# Radio.net
KiCad netlist of a schematic drawn in Altium Designer
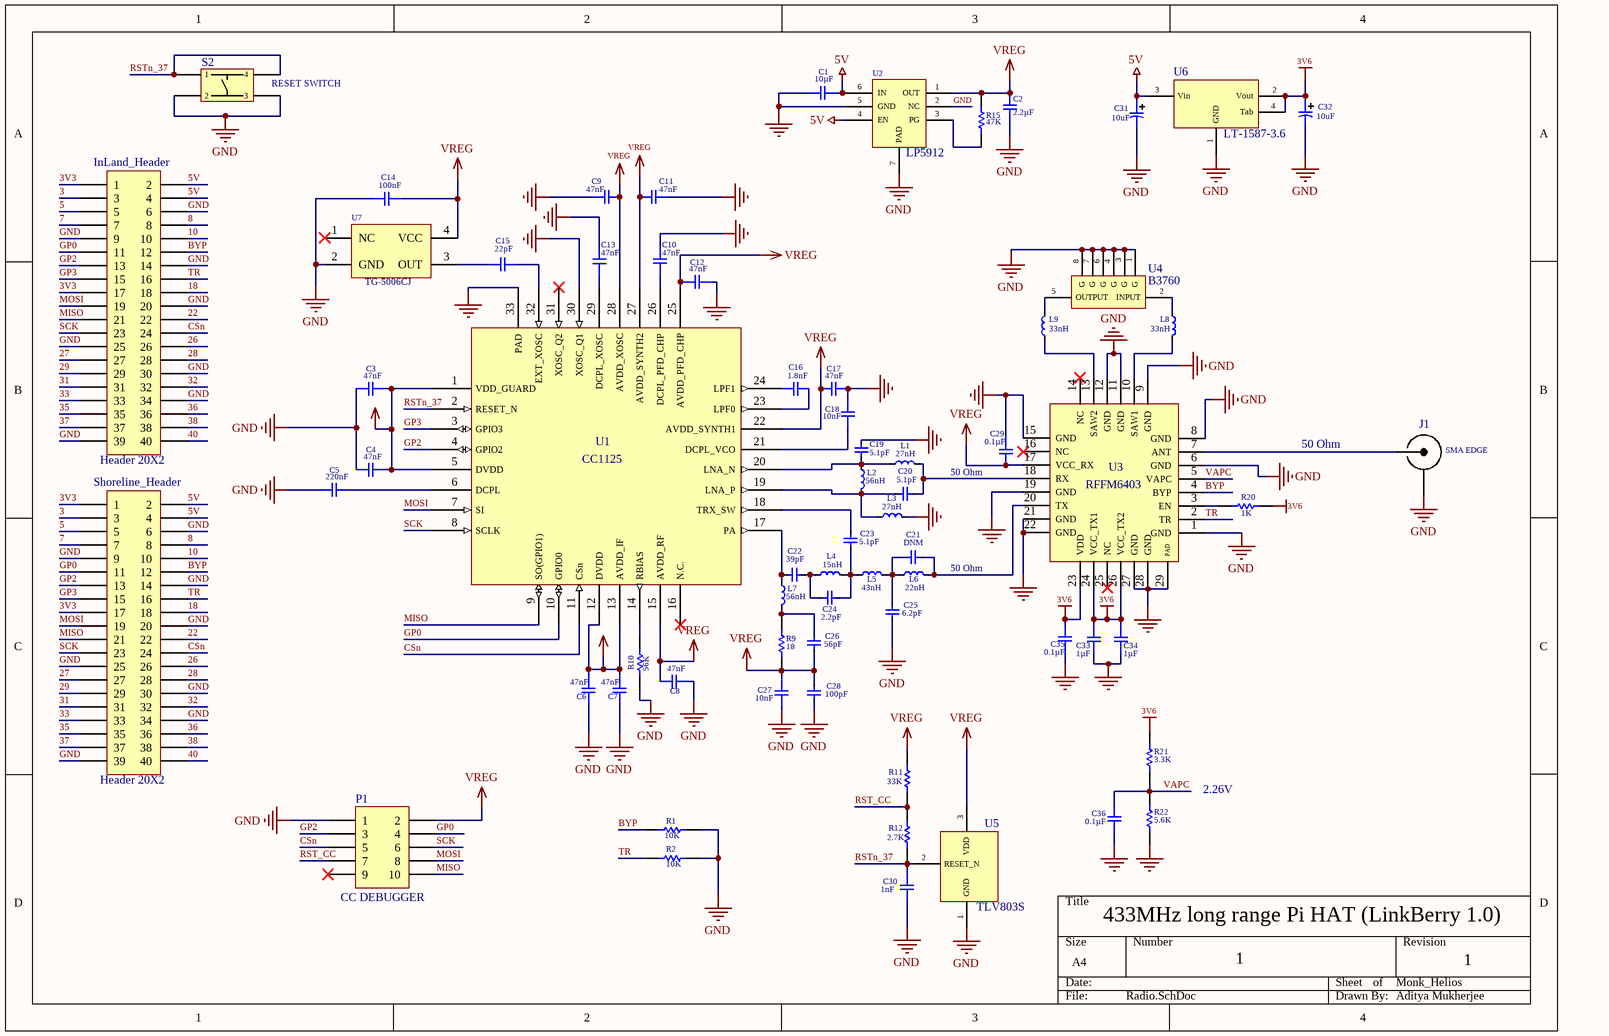
[diagram p0: Radio.SchDoc]

(export (version "E")
  (design (tool "Eeschema 10.0.6"))
  (components
    (comp (ref "C1")
      (value "10µF")
      (footprint "SMD-0603C")
      (description "CAP CER 0.1UF 16V X7R 0603")
      (fields
        (field (name "DIGI-KEY PART NUMBER") "490-5796-1-ND")
        (field (name "PART NUMBER") "GCJ188R71C104KA01D")
      )
      (libsource (lib "capacitor_murata_0603") (part "GCJ188R71C104KA01D"))
    )
    (comp (ref "C2")
      (value "2.2µF")
      (footprint "SMD-0603C")
      (description "CAP CER 0.1UF 16V X7R 0603")
      (fields
        (field (name "DIGI-KEY PART NUMBER") "490-5796-1-ND")
        (field (name "PART NUMBER") "GCJ188R71C104KA01D")
      )
      (libsource (lib "capacitor_murata_0603") (part "GCJ188R71C104KA01D"))
    )
    (comp (ref "C3")
      (value "47nF")
      (footprint "SMD-0402C")
      (description "CAP CER 1UF 10V X7S 0402")
      (fields
        (field (name "DIGI-KEY PART NUMBER") "490-13409-1-ND")
        (field (name "PART NUMBER") "GCM155C71A105KE38D")
      )
      (libsource (lib "capacitor_murata_0402") (part "GCM155C71A105KE38D"))
    )
    (comp (ref "C4")
      (value "47nF")
      (footprint "SMD-0402C")
      (description "CAP CER 1UF 10V X7S 0402")
      (fields
        (field (name "DIGI-KEY PART NUMBER") "490-13409-1-ND")
        (field (name "PART NUMBER") "GCM155C71A105KE38D")
      )
      (libsource (lib "capacitor_murata_0402") (part "GCM155C71A105KE38D"))
    )
    (comp (ref "C5")
      (value "220nF")
      (footprint "SMD-0402C")
      (description "CAP CER 1UF 10V X7S 0402")
      (fields
        (field (name "DIGI-KEY PART NUMBER") "490-13409-1-ND")
        (field (name "PART NUMBER") "GCM155C71A105KE38D")
      )
      (libsource (lib "capacitor_murata_0402") (part "GCM155C71A105KE38D"))
    )
    (comp (ref "C6")
      (value "47nF")
      (footprint "SMD-0402C")
      (description "CAP CER 1UF 10V X7S 0402")
      (fields
        (field (name "DIGI-KEY PART NUMBER") "490-13409-1-ND")
        (field (name "PART NUMBER") "GCM155C71A105KE38D")
      )
      (libsource (lib "capacitor_murata_0402") (part "GCM155C71A105KE38D"))
    )
    (comp (ref "C7")
      (value "47nF")
      (footprint "SMD-0402C")
      (description "CAP CER 1UF 10V X7S 0402")
      (fields
        (field (name "DIGI-KEY PART NUMBER") "490-13409-1-ND")
        (field (name "PART NUMBER") "GCM155C71A105KE38D")
      )
      (libsource (lib "capacitor_murata_0402") (part "GCM155C71A105KE38D"))
    )
    (comp (ref "C8")
      (value "47nF")
      (footprint "SMD-0402C")
      (description "CAP CER 1UF 10V X7S 0402")
      (fields
        (field (name "DIGI-KEY PART NUMBER") "490-13409-1-ND")
        (field (name "PART NUMBER") "GCM155C71A105KE38D")
      )
      (libsource (lib "capacitor_murata_0402") (part "GCM155C71A105KE38D"))
    )
    (comp (ref "C9")
      (value "47nF")
      (footprint "SMD-0402C")
      (description "CAP CER 1UF 10V X7S 0402")
      (fields
        (field (name "DIGI-KEY PART NUMBER") "490-13409-1-ND")
        (field (name "PART NUMBER") "GCM155C71A105KE38D")
      )
      (libsource (lib "capacitor_murata_0402") (part "GCM155C71A105KE38D"))
    )
    (comp (ref "C10")
      (value "47nF")
      (footprint "SMD-0402C")
      (description "CAP CER 1UF 10V X7S 0402")
      (fields
        (field (name "DIGI-KEY PART NUMBER") "490-13409-1-ND")
        (field (name "PART NUMBER") "GCM155C71A105KE38D")
      )
      (libsource (lib "capacitor_murata_0402") (part "GCM155C71A105KE38D"))
    )
    (comp (ref "C11")
      (value "47nF")
      (footprint "SMD-0402C")
      (description "CAP CER 1UF 10V X7S 0402")
      (fields
        (field (name "DIGI-KEY PART NUMBER") "490-13409-1-ND")
        (field (name "PART NUMBER") "GCM155C71A105KE38D")
      )
      (libsource (lib "capacitor_murata_0402") (part "GCM155C71A105KE38D"))
    )
    (comp (ref "C12")
      (value "47nF")
      (footprint "SMD-0402C")
      (description "CAP CER 1UF 10V X7S 0402")
      (fields
        (field (name "DIGI-KEY PART NUMBER") "490-13409-1-ND")
        (field (name "PART NUMBER") "GCM155C71A105KE38D")
      )
      (libsource (lib "capacitor_murata_0402") (part "GCM155C71A105KE38D"))
    )
    (comp (ref "C13")
      (value "47nF")
      (footprint "SMD-0402C")
      (description "CAP CER 1UF 10V X7S 0402")
      (fields
        (field (name "DIGI-KEY PART NUMBER") "490-13409-1-ND")
        (field (name "PART NUMBER") "GCM155C71A105KE38D")
      )
      (libsource (lib "capacitor_murata_0402") (part "GCM155C71A105KE38D"))
    )
    (comp (ref "C14")
      (value "100nF")
      (footprint "SMD-0402C")
      (description "CAP CER 1UF 10V X7S 0402")
      (fields
        (field (name "DIGI-KEY PART NUMBER") "490-13409-1-ND")
        (field (name "PART NUMBER") "GCM155C71A105KE38D")
      )
      (libsource (lib "capacitor_murata_0402") (part "GCM155C71A105KE38D"))
    )
    (comp (ref "C15")
      (value "22pF")
      (footprint "SMD-0402C")
      (description "CAP CER 1UF 50V NP0 0402")
      (fields
        (field (name "DIGI-KEY PART NUMBER") "490-13409-1-ND")
        (field (name "PART NUMBER") "GCM155C71A105KE38D")
      )
      (libsource (lib "capacitor_murata_0402") (part "GCM155C71A105KE38D"))
    )
    (comp (ref "C16")
      (value "1.8nF")
      (footprint "SMD-0402C")
      (description "CAP CER 1.8nF 10V X7S 0402")
      (fields
        (field (name "DIGI-KEY PART NUMBER") "490-13409-1-ND")
        (field (name "PART NUMBER") "GCM155C71A105KE38D")
      )
      (libsource (lib "capacitor_murata_0402") (part "GCM155C71A105KE38D"))
    )
    (comp (ref "C17")
      (value "47nF")
      (footprint "SMD-0402C")
      (description "CAP CER 1UF 10V X7S 0402")
      (fields
        (field (name "DIGI-KEY PART NUMBER") "490-13409-1-ND")
        (field (name "PART NUMBER") "GCM155C71A105KE38D")
      )
      (libsource (lib "capacitor_murata_0402") (part "GCM155C71A105KE38D"))
    )
    (comp (ref "C18")
      (value "10nF")
      (footprint "SMD-0402C")
      (description "CAP CER 1UF 10V X7S 0402")
      (fields
        (field (name "DIGI-KEY PART NUMBER") "490-13409-1-ND")
        (field (name "PART NUMBER") "GCM155C71A105KE38D")
      )
      (libsource (lib "capacitor_murata_0402") (part "GCM155C71A105KE38D"))
    )
    (comp (ref "C19")
      (value "5.1pF")
      (footprint "0402")
      (description "Ceramic Chip Capacitor - Standard")
      (fields (field (name "Comment") "C0402") (field (name "PUBLISHER") "Altium Limited"))
      (libsource (lib "KEMET Chip Capacitor") (part "C0402"))
    )
    (comp (ref "C20")
      (value "5.1pF")
      (footprint "0402")
      (description "Ceramic Chip Capacitor - Standard")
      (fields (field (name "Comment") "C0402") (field (name "PUBLISHER") "Altium Limited"))
      (libsource (lib "KEMET Chip Capacitor") (part "C0402"))
    )
    (comp (ref "C21")
      (value "DNM")
      (footprint "0402")
      (description "Ceramic Chip Capacitor - Standard")
      (fields (field (name "Comment") "C0402") (field (name "PUBLISHER") "Altium Limited"))
      (libsource (lib "KEMET Chip Capacitor") (part "C0402"))
    )
    (comp (ref "C22")
      (value "39pF")
      (footprint "0402")
      (description "Ceramic Chip Capacitor - Standard")
      (fields (field (name "Comment") "C0402") (field (name "PUBLISHER") "Altium Limited"))
      (libsource (lib "KEMET Chip Capacitor") (part "C0402"))
    )
    (comp (ref "C23")
      (value "5.1pF")
      (footprint "0402")
      (description "Ceramic Chip Capacitor - Standard")
      (fields (field (name "Comment") "C0402") (field (name "PUBLISHER") "Altium Limited"))
      (libsource (lib "KEMET Chip Capacitor") (part "C0402"))
    )
    (comp (ref "C24")
      (value "2.2pF")
      (footprint "0402")
      (description "Ceramic Chip Capacitor - Standard")
      (fields (field (name "Comment") "C0402") (field (name "PUBLISHER") "Altium Limited"))
      (libsource (lib "KEMET Chip Capacitor") (part "C0402"))
    )
    (comp (ref "C25")
      (value "6.2pF")
      (footprint "0402")
      (description "Ceramic Chip Capacitor - Standard")
      (fields (field (name "Comment") "C0402") (field (name "PUBLISHER") "Altium Limited"))
      (libsource (lib "KEMET Chip Capacitor") (part "C0402"))
    )
    (comp (ref "C26")
      (value "56pF")
      (footprint "0402")
      (description "Ceramic Chip Capacitor - Standard")
      (fields (field (name "Comment") "C0402") (field (name "PUBLISHER") "Altium Limited"))
      (libsource (lib "KEMET Chip Capacitor") (part "C0402"))
    )
    (comp (ref "C27")
      (value "10nF")
      (footprint "SMD-0402C")
      (description "CAP CER 1UF 10V X7S 0402")
      (fields
        (field (name "DIGI-KEY PART NUMBER") "490-13409-1-ND")
        (field (name "PART NUMBER") "GCM155C71A105KE38D")
      )
      (libsource (lib "capacitor_murata_0402") (part "GCM155C71A105KE38D"))
    )
    (comp (ref "C28")
      (value "100pF")
      (footprint "0402")
      (description "Ceramic Chip Capacitor - Standard")
      (fields (field (name "Comment") "C0402") (field (name "PUBLISHER") "Altium Limited"))
      (libsource (lib "KEMET Chip Capacitor") (part "C0402"))
    )
    (comp (ref "C29")
      (value "0.1µF")
      (footprint "SMD-0603C")
      (description "CAP CER 0.1UF 16V X7R 0603")
      (fields
        (field (name "DIGI-KEY PART NUMBER") "490-5796-1-ND")
        (field (name "PART NUMBER") "GCJ188R71C104KA01D")
      )
      (libsource (lib "capacitor_murata_0603") (part "GCJ188R71C104KA01D"))
    )
    (comp (ref "C30")
      (value "1nF")
      (footprint "SMD-0402C")
      (description "CAP CER 1UF 10V X7S 0402")
      (fields
        (field (name "DIGI-KEY PART NUMBER") "490-13409-1-ND")
        (field (name "PART NUMBER") "GCM155C71A105KE38D")
      )
      (libsource (lib "capacitor_murata_0402") (part "GCM155C71A105KE38D"))
    )
    (comp (ref "C31")
      (value "Component_1")
      (footprint "PCBComponent_1")
      (fields (field (name "ALTIUM_UNNAMED_1") "10uF"))
      (libsource (lib "AVX_tantalium_1505") (part "Component_1"))
    )
    (comp (ref "C32")
      (value "Component_1")
      (footprint "PCBComponent_1")
      (fields (field (name "ALTIUM_UNNAMED_1") "10uF"))
      (libsource (lib "AVX_tantalium_1505") (part "Component_1"))
    )
    (comp (ref "C33")
      (value "1µF")
      (footprint "SMD-0603C")
      (description "CAP CER 1UF 16V X7R 0603")
      (fields
        (field (name "DIGI-KEY PART NUMBER") "490-5796-1-ND")
        (field (name "PART NUMBER") "GCJ188R71C104KA01D")
      )
      (libsource (lib "capacitor_murata_0603") (part "GCJ188R71C104KA01D"))
    )
    (comp (ref "C34")
      (value "1µF")
      (footprint "SMD-0603C")
      (description "CAP CER 1UF 16V X7R 0603")
      (fields
        (field (name "DIGI-KEY PART NUMBER") "490-5796-1-ND")
        (field (name "PART NUMBER") "GCJ188R71C104KA01D")
      )
      (libsource (lib "capacitor_murata_0603") (part "GCJ188R71C104KA01D"))
    )
    (comp (ref "C35")
      (value "0.1µF")
      (footprint "SMD-0603C")
      (description "CAP CER 0.1UF 16V X7R 0603")
      (fields
        (field (name "DIGI-KEY PART NUMBER") "490-5796-1-ND")
        (field (name "PART NUMBER") "GCJ188R71C104KA01D")
      )
      (libsource (lib "capacitor_murata_0603") (part "GCJ188R71C104KA01D"))
    )
    (comp (ref "C36")
      (value "0.1µF")
      (footprint "SMD-0603C")
      (description "CAP CER 0.1UF 16V X7R 0603")
      (fields
        (field (name "DIGI-KEY PART NUMBER") "490-5796-1-ND")
        (field (name "PART NUMBER") "GCJ188R71C104KA01D")
      )
      (libsource (lib "capacitor_murata_0603") (part "GCJ188R71C104KA01D"))
    )
    (comp (ref "InLand_Header")
      (value "Header 20X2")
      (footprint "HDR2X20")
      (description "Header, 20-Pin, Dual row")
      (fields (field (name "PUBLISHER") "Altium Limited"))
      (libsource (lib "Miscellaneous Connectors") (part "Header 20X2"))
    )
    (comp (ref "J1")
      (value "SMA EDGE")
      (footprint "PCBComponent_1")
      (libsource (lib "SMA_small") (part "Component_1"))
    )
    (comp (ref "L1")
      (value "Component_1")
      (footprint "LQW15AN80")
      (fields (field (name "ALTIUM_UNNAMED_1") "27nH"))
      (libsource (lib "LQW15AN80") (part "Component_1"))
    )
    (comp (ref "L2")
      (value "Component_1")
      (footprint "LQW15AW80")
      (fields (field (name "ALTIUM_UNNAMED_1") "56nH"))
      (libsource (lib "LQW15AW80") (part "Component_1"))
    )
    (comp (ref "L3")
      (value "Component_1")
      (footprint "LQW15AN80")
      (fields (field (name "ALTIUM_UNNAMED_1") "27nH"))
      (libsource (lib "LQW15AN80") (part "Component_1"))
    )
    (comp (ref "L4")
      (value "Component_1")
      (footprint "LQW15AN80")
      (fields (field (name "ALTIUM_UNNAMED_1") "15nH"))
      (libsource (lib "LQW15AN80") (part "Component_1"))
    )
    (comp (ref "L5")
      (value "Component_1")
      (footprint "LQW15AN80")
      (fields (field (name "ALTIUM_UNNAMED_1") "43nH"))
      (libsource (lib "LQW15AN80") (part "Component_1"))
    )
    (comp (ref "L6")
      (value "Component_1")
      (footprint "LQW15AN80")
      (fields (field (name "ALTIUM_UNNAMED_1") "22nH"))
      (libsource (lib "LQW15AN80") (part "Component_1"))
    )
    (comp (ref "L7")
      (value "Component_1")
      (footprint "LQW15AW80")
      (fields (field (name "ALTIUM_UNNAMED_1") "56nH"))
      (libsource (lib "LQW15AW80") (part "Component_1"))
    )
    (comp (ref "L8")
      (value "Component_1")
      (footprint "LQW15AN80")
      (fields (field (name "ALTIUM_UNNAMED_1") "33nH"))
      (libsource (lib "LQW15AN80") (part "Component_1"))
    )
    (comp (ref "L9")
      (value "Component_1")
      (footprint "LQW15AN80")
      (fields (field (name "ALTIUM_UNNAMED_1") "33nH"))
      (libsource (lib "LQW15AN80") (part "Component_1"))
    )
    (comp (ref "P1")
      (value "CC DEBUGGER")
      (footprint "HDR2X5")
      (description "Header, 5-Pin, Dual row")
      (fields (field (name "PUBLISHER") "Altium Limited"))
      (libsource (lib "Miscellaneous Connectors") (part "Header 5X2"))
    )
    (comp (ref "R1")
      (value "10K")
      (footprint "2-0402")
      (fields (field (name "ALTIUM_UNNAMED_1") "10K") (field (name "PUBLISHER") "Altium Limited"))
      (libsource (lib "Panasonic Resistor") (part "ERJ2RE"))
    )
    (comp (ref "R2")
      (value "10K")
      (footprint "2-0402")
      (fields (field (name "ALTIUM_UNNAMED_1") "10K") (field (name "PUBLISHER") "Altium Limited"))
      (libsource (lib "Panasonic Resistor") (part "ERJ2RE"))
    )
    (comp (ref "R9")
      (value "18")
      (footprint "2-0402")
      (description "Thick Film Chip Resistor, 1 Ohm to 2.2M Ohm Range, 5% Tolerance, 0402 Size, 0.063 W")
      (fields (field (name "Comment") "ERJ2GE") (field (name "PUBLISHER") "Altium Limited"))
      (libsource (lib "Panasonic Resistor") (part "ERJ2GE"))
    )
    (comp (ref "R10")
      (value "56K")
      (footprint "2-0402")
      (description "Thick Film Chip Resistor, 1 Ohm to 2.2M Ohm Range, 5% Tolerance, 0402 Size, 0.063 W")
      (fields (field (name "Comment") "ERJ2GE") (field (name "PUBLISHER") "Altium Limited"))
      (libsource (lib "Panasonic Resistor") (part "ERJ2GE"))
    )
    (comp (ref "R11")
      (value "10K")
      (footprint "2-0402")
      (fields (field (name "ALTIUM_UNNAMED_1") "33K") (field (name "PUBLISHER") "Altium Limited"))
      (libsource (lib "Panasonic Resistor") (part "ERJ2RE"))
    )
    (comp (ref "R12")
      (value "10K")
      (footprint "2-0402")
      (fields (field (name "ALTIUM_UNNAMED_1") "2.7K") (field (name "PUBLISHER") "Altium Limited"))
      (libsource (lib "Panasonic Resistor") (part "ERJ2RE"))
    )
    (comp (ref "R15")
      (value "47K")
      (footprint "ERA-0603")
      (fields (field (name "Comment") "ERA3Y") (field (name "PUBLISHER") "Altium Limited"))
      (libsource (lib "Panasonic Resistor") (part "ERA3Y"))
    )
    (comp (ref "R20")
      (value "1K")
      (footprint "2-0402")
      (description "Thick Film Chip Resistor, 1 Ohm to 2.2M Ohm Range, 5% Tolerance, 0402 Size, 0.063 W")
      (fields (field (name "Comment") "ERJ2GE") (field (name "PUBLISHER") "Altium Limited"))
      (libsource (lib "Panasonic Resistor") (part "ERJ2GE"))
    )
    (comp (ref "R21")
      (value "3.3K")
      (footprint "2-0402")
      (description "Thick Film Chip Resistor, 1 Ohm to 2.2M Ohm Range, 5% Tolerance, 0402 Size, 0.063 W")
      (fields (field (name "Comment") "ERJ2GE") (field (name "PUBLISHER") "Altium Limited"))
      (libsource (lib "Panasonic Resistor") (part "ERJ2GE"))
    )
    (comp (ref "R22")
      (value "5.6K")
      (footprint "2-0402")
      (description "Thick Film Chip Resistor, 1 Ohm to 2.2M Ohm Range, 5% Tolerance, 0402 Size, 0.063 W")
      (fields (field (name "Comment") "ERJ2GE") (field (name "PUBLISHER") "Altium Limited"))
      (libsource (lib "Panasonic Resistor") (part "ERJ2GE"))
    )
    (comp (ref "S2")
      (value "RESET SWITCH")
      (footprint "PCBComponent_1")
      (libsource (lib "panasonic_90deg_tactile") (part "Component_1"))
    )
    (comp (ref "Shoreline_Header")
      (value "Header 20X2")
      (footprint "HDR2X20")
      (description "Header, 20-Pin, Dual row")
      (fields (field (name "PUBLISHER") "Altium Limited"))
      (libsource (lib "Miscellaneous Connectors") (part "Header 20X2"))
    )
    (comp (ref "U1") (value "CC1125") (footprint "CC1125 QFN") (libsource (lib "CC1125") (part "CC1125")))
    (comp (ref "U2") (value "LP5912") (footprint "LP5912_WSON") (libsource (lib "5912") (part "LP5912")))
    (comp (ref "U3")
      (value "RFFM6403")
      (footprint "PCBComponent_1")
      (libsource (lib "RFFM6403") (part "RFFM6403"))
    )
    (comp (ref "U4")
      (value "B3760")
      (footprint "PCBComponent_1")
      (libsource (lib "B3760_SAW_filter") (part "Component_1"))
    )
    (comp (ref "U5")
      (value "TLV803S")
      (footprint "SOT95P237X110-3N")
      (libsource (lib "TLV803S") (part "Component_1"))
    )
    (comp (ref "U6")
      (value "LT1587-3.6")
      (footprint "LT1587")
      (fields (field (name "ALTIUM_UNNAMED_1") "LT-1587-3.6"))
      (libsource (lib "LT1587-3.6") (part "Component_1"))
    )
    (comp (ref "U7")
      (value "TG-5006CJ")
      (footprint "TG-5006CJ")
      (libsource (lib "TG-5006(TCXO)") (part "TG-5006CJ"))
    )
  )
  (nets
    (net (code "1") (name "/3") (class "Default")
      (node (ref "InLand_Header") (pin "3") (pinfunction "3_3") (pintype "passive"))
      (node (ref "Shoreline_Header") (pin "3") (pinfunction "3_3") (pintype "passive"))
    )
    (net (code "2") (name "/3V3") (class "Default")
      (node (ref "InLand_Header") (pin "1") (pinfunction "1_1") (pintype "passive"))
      (node (ref "InLand_Header") (pin "17") (pinfunction "17_17") (pintype "passive"))
      (node (ref "Shoreline_Header") (pin "1") (pinfunction "1_1") (pintype "passive"))
      (node (ref "Shoreline_Header") (pin "17") (pinfunction "17_17") (pintype "passive"))
    )
    (net (code "3") (name "/5") (class "Default")
      (node (ref "InLand_Header") (pin "5") (pinfunction "5_5") (pintype "passive"))
      (node (ref "Shoreline_Header") (pin "5") (pinfunction "5_5") (pintype "passive"))
    )
    (net (code "4") (name "/7") (class "Default")
      (node (ref "InLand_Header") (pin "7") (pinfunction "7_7") (pintype "passive"))
      (node (ref "Shoreline_Header") (pin "7") (pinfunction "7_7") (pintype "passive"))
    )
    (net (code "5") (name "/8") (class "Default")
      (node (ref "InLand_Header") (pin "8") (pinfunction "8_8") (pintype "passive"))
      (node (ref "Shoreline_Header") (pin "8") (pinfunction "8_8") (pintype "passive"))
    )
    (net (code "6") (name "/10") (class "Default")
      (node (ref "InLand_Header") (pin "10") (pinfunction "10_10") (pintype "passive"))
      (node (ref "Shoreline_Header") (pin "10") (pinfunction "10_10") (pintype "passive"))
    )
    (net (code "7") (name "/18") (class "Default")
      (node (ref "InLand_Header") (pin "18") (pinfunction "18_18") (pintype "passive"))
      (node (ref "Shoreline_Header") (pin "18") (pinfunction "18_18") (pintype "passive"))
    )
    (net (code "8") (name "/22") (class "Default")
      (node (ref "InLand_Header") (pin "22") (pinfunction "22_22") (pintype "passive"))
      (node (ref "Shoreline_Header") (pin "22") (pinfunction "22_22") (pintype "passive"))
    )
    (net (code "9") (name "/26") (class "Default")
      (node (ref "InLand_Header") (pin "26") (pinfunction "26_26") (pintype "passive"))
      (node (ref "Shoreline_Header") (pin "26") (pinfunction "26_26") (pintype "passive"))
    )
    (net (code "10") (name "/27") (class "Default")
      (node (ref "InLand_Header") (pin "27") (pinfunction "27_27") (pintype "passive"))
      (node (ref "Shoreline_Header") (pin "27") (pinfunction "27_27") (pintype "passive"))
    )
    (net (code "11") (name "/28") (class "Default")
      (node (ref "InLand_Header") (pin "28") (pinfunction "28_28") (pintype "passive"))
      (node (ref "Shoreline_Header") (pin "28") (pinfunction "28_28") (pintype "passive"))
    )
    (net (code "12") (name "/29") (class "Default")
      (node (ref "InLand_Header") (pin "29") (pinfunction "29_29") (pintype "passive"))
      (node (ref "Shoreline_Header") (pin "29") (pinfunction "29_29") (pintype "passive"))
    )
    (net (code "13") (name "/31") (class "Default")
      (node (ref "InLand_Header") (pin "31") (pinfunction "31_31") (pintype "passive"))
      (node (ref "Shoreline_Header") (pin "31") (pinfunction "31_31") (pintype "passive"))
    )
    (net (code "14") (name "/32") (class "Default")
      (node (ref "InLand_Header") (pin "32") (pinfunction "32_32") (pintype "passive"))
      (node (ref "Shoreline_Header") (pin "32") (pinfunction "32_32") (pintype "passive"))
    )
    (net (code "15") (name "/33") (class "Default")
      (node (ref "InLand_Header") (pin "33") (pinfunction "33_33") (pintype "passive"))
      (node (ref "Shoreline_Header") (pin "33") (pinfunction "33_33") (pintype "passive"))
    )
    (net (code "16") (name "/35") (class "Default")
      (node (ref "InLand_Header") (pin "35") (pinfunction "35_35") (pintype "passive"))
      (node (ref "Shoreline_Header") (pin "35") (pinfunction "35_35") (pintype "passive"))
    )
    (net (code "17") (name "/36") (class "Default")
      (node (ref "InLand_Header") (pin "36") (pinfunction "36_36") (pintype "passive"))
      (node (ref "Shoreline_Header") (pin "36") (pinfunction "36_36") (pintype "passive"))
    )
    (net (code "18") (name "/37") (class "Default")
      (node (ref "InLand_Header") (pin "37") (pinfunction "37_37") (pintype "passive"))
      (node (ref "Shoreline_Header") (pin "37") (pinfunction "37_37") (pintype "passive"))
    )
    (net (code "19") (name "/38") (class "Default")
      (node (ref "InLand_Header") (pin "38") (pinfunction "38_38") (pintype "passive"))
      (node (ref "Shoreline_Header") (pin "38") (pinfunction "38_38") (pintype "passive"))
    )
    (net (code "20") (name "/40") (class "Default")
      (node (ref "InLand_Header") (pin "40") (pinfunction "40_40") (pintype "passive"))
      (node (ref "Shoreline_Header") (pin "40") (pinfunction "40_40") (pintype "passive"))
    )
    (net (code "21") (name "/BYP") (class "Default")
      (node (ref "InLand_Header") (pin "12") (pinfunction "12_12") (pintype "passive"))
      (node (ref "R1") (pin "2") (pinfunction "2_2") (pintype "passive"))
      (node (ref "Shoreline_Header") (pin "12") (pinfunction "12_12") (pintype "passive"))
      (node (ref "U3") (pin "4") (pinfunction "BYP_4") (pintype "passive"))
    )
    (net (code "22") (name "/CSn") (class "Default")
      (node (ref "InLand_Header") (pin "24") (pinfunction "24_24") (pintype "passive"))
      (node (ref "P1") (pin "5") (pinfunction "5_5") (pintype "passive"))
      (node (ref "Shoreline_Header") (pin "24") (pinfunction "24_24") (pintype "passive"))
      (node (ref "U1") (pin "11") (pinfunction "CSn_11") (pintype "input"))
    )
    (net (code "23") (name "/GP0") (class "Default")
      (node (ref "InLand_Header") (pin "11") (pinfunction "11_11") (pintype "passive"))
      (node (ref "P1") (pin "4") (pinfunction "4_4") (pintype "passive"))
      (node (ref "Shoreline_Header") (pin "11") (pinfunction "11_11") (pintype "passive"))
      (node (ref "U1") (pin "10") (pinfunction "GPIO0_10") (pintype "bidirectional"))
    )
    (net (code "24") (name "/GP2") (class "Default")
      (node (ref "InLand_Header") (pin "13") (pinfunction "13_13") (pintype "passive"))
      (node (ref "P1") (pin "3") (pinfunction "3_3") (pintype "passive"))
      (node (ref "Shoreline_Header") (pin "13") (pinfunction "13_13") (pintype "passive"))
      (node (ref "U1") (pin "4") (pinfunction "GPIO2_4") (pintype "bidirectional"))
    )
    (net (code "25") (name "/GP3") (class "Default")
      (node (ref "InLand_Header") (pin "15") (pinfunction "15_15") (pintype "passive"))
      (node (ref "Shoreline_Header") (pin "15") (pinfunction "15_15") (pintype "passive"))
      (node (ref "U1") (pin "3") (pinfunction "GPIO3_3") (pintype "bidirectional"))
    )
    (net (code "26") (name "/MISO") (class "Default")
      (node (ref "InLand_Header") (pin "21") (pinfunction "21_21") (pintype "passive"))
      (node (ref "P1") (pin "10") (pinfunction "10_10") (pintype "passive"))
      (node (ref "Shoreline_Header") (pin "21") (pinfunction "21_21") (pintype "passive"))
      (node (ref "U1") (pin "9") (pinfunction "SO(GPIO1)_9") (pintype "bidirectional"))
    )
    (net (code "27") (name "/MOSI") (class "Default")
      (node (ref "InLand_Header") (pin "19") (pinfunction "19_19") (pintype "passive"))
      (node (ref "P1") (pin "8") (pinfunction "8_8") (pintype "passive"))
      (node (ref "Shoreline_Header") (pin "19") (pinfunction "19_19") (pintype "passive"))
      (node (ref "U1") (pin "7") (pinfunction "SI_7") (pintype "input"))
    )
    (net (code "28") (name "/RST_CC") (class "Default")
      (node (ref "P1") (pin "7") (pinfunction "7_7") (pintype "passive"))
      (node (ref "R11") (pin "1") (pinfunction "1_1") (pintype "passive"))
      (node (ref "R12") (pin "2") (pinfunction "2_2") (pintype "passive"))
    )
    (net (code "29") (name "/RSTn_37") (class "Default")
      (node (ref "C30") (pin "1") (pinfunction "1_1") (pintype "passive"))
      (node (ref "R12") (pin "1") (pinfunction "1_1") (pintype "passive"))
      (node (ref "S2") (pin "1") (pinfunction "1_1") (pintype "passive"))
      (node (ref "S2") (pin "4") (pinfunction "4_4") (pintype "passive"))
      (node (ref "U1") (pin "2") (pinfunction "RESET_N_2") (pintype "input"))
      (node (ref "U5") (pin "2") (pinfunction "RESET_N_2") (pintype "passive"))
    )
    (net (code "30") (name "/SCK") (class "Default")
      (node (ref "InLand_Header") (pin "23") (pinfunction "23_23") (pintype "passive"))
      (node (ref "P1") (pin "6") (pinfunction "6_6") (pintype "passive"))
      (node (ref "Shoreline_Header") (pin "23") (pinfunction "23_23") (pintype "passive"))
      (node (ref "U1") (pin "8") (pinfunction "SCLK_8") (pintype "input"))
    )
    (net (code "31") (name "/TR") (class "Default")
      (node (ref "InLand_Header") (pin "16") (pinfunction "16_16") (pintype "passive"))
      (node (ref "R2") (pin "2") (pinfunction "2_2") (pintype "passive"))
      (node (ref "Shoreline_Header") (pin "16") (pinfunction "16_16") (pintype "passive"))
      (node (ref "U3") (pin "2") (pinfunction "TR_2") (pintype "passive"))
    )
    (net (code "32") (name "/VAPC") (class "Default")
      (node (ref "C36") (pin "2") (pinfunction "2_2") (pintype "passive"))
      (node (ref "R21") (pin "1") (pinfunction "1_1") (pintype "passive"))
      (node (ref "R22") (pin "2") (pinfunction "2_2") (pintype "passive"))
      (node (ref "U3") (pin "5") (pinfunction "VAPC_5") (pintype "passive"))
    )
    (net (code "33") (name "3V6") (class "Default")
      (node (ref "C32") (pin "1") (pinfunction "1_1") (pintype "passive"))
      (node (ref "C33") (pin "1") (pinfunction "1_1") (pintype "passive"))
      (node (ref "C34") (pin "1") (pinfunction "1_1") (pintype "passive"))
      (node (ref "C35") (pin "2") (pinfunction "2_2") (pintype "passive"))
      (node (ref "R20") (pin "1") (pinfunction "1_1") (pintype "passive"))
      (node (ref "R21") (pin "2") (pinfunction "2_2") (pintype "passive"))
      (node (ref "U3") (pin "23") (pinfunction "VDD_23") (pintype "passive"))
      (node (ref "U3") (pin "24") (pinfunction "VCC_TX1_24") (pintype "passive"))
      (node (ref "U3") (pin "26") (pinfunction "VCC_TX2_26") (pintype "passive"))
      (node (ref "U6") (pin "2") (pinfunction "Vout_2") (pintype "passive"))
      (node (ref "U6") (pin "4") (pinfunction "Tab_4") (pintype "passive"))
    )
    (net (code "34") (name "5V") (class "Default")
      (node (ref "C1") (pin "1") (pinfunction "1_1") (pintype "passive"))
      (node (ref "C31") (pin "1") (pinfunction "1_1") (pintype "passive"))
      (node (ref "InLand_Header") (pin "2") (pinfunction "2_2") (pintype "passive"))
      (node (ref "InLand_Header") (pin "4") (pinfunction "4_4") (pintype "passive"))
      (node (ref "Shoreline_Header") (pin "2") (pinfunction "2_2") (pintype "passive"))
      (node (ref "Shoreline_Header") (pin "4") (pinfunction "4_4") (pintype "passive"))
      (node (ref "U2") (pin "4") (pinfunction "EN_4") (pintype "passive"))
      (node (ref "U2") (pin "6") (pinfunction "IN_6") (pintype "passive"))
      (node (ref "U6") (pin "3") (pinfunction "Vin_3") (pintype "passive"))
    )
    (net (code "35") (name "GND") (class "Default")
      (node (ref "C1") (pin "2") (pinfunction "2_2") (pintype "passive"))
      (node (ref "C10") (pin "2") (pinfunction "2_2") (pintype "passive"))
      (node (ref "C11") (pin "2") (pinfunction "2_2") (pintype "passive"))
      (node (ref "C12") (pin "1") (pinfunction "1_1") (pintype "passive"))
      (node (ref "C13") (pin "2") (pinfunction "2_2") (pintype "passive"))
      (node (ref "C14") (pin "2") (pinfunction "2_2") (pintype "passive"))
      (node (ref "C17") (pin "1") (pinfunction "1_1") (pintype "passive"))
      (node (ref "C18") (pin "1") (pinfunction "1_1") (pintype "passive"))
      (node (ref "C19") (pin "2") (pinfunction "2_2") (pintype "passive"))
      (node (ref "C2") (pin "2") (pinfunction "2_2") (pintype "passive"))
      (node (ref "C25") (pin "1") (pinfunction "1_1") (pintype "passive"))
      (node (ref "C27") (pin "2") (pinfunction "2_2") (pintype "passive"))
      (node (ref "C28") (pin "1") (pinfunction "1_1") (pintype "passive"))
      (node (ref "C29") (pin "1") (pinfunction "1_1") (pintype "passive"))
      (node (ref "C3") (pin "1") (pinfunction "1_1") (pintype "passive"))
      (node (ref "C30") (pin "2") (pinfunction "2_2") (pintype "passive"))
      (node (ref "C31") (pin "2") (pinfunction "2_2") (pintype "passive"))
      (node (ref "C32") (pin "2") (pinfunction "2_2") (pintype "passive"))
      (node (ref "C33") (pin "2") (pinfunction "2_2") (pintype "passive"))
      (node (ref "C34") (pin "2") (pinfunction "2_2") (pintype "passive"))
      (node (ref "C35") (pin "1") (pinfunction "1_1") (pintype "passive"))
      (node (ref "C36") (pin "1") (pinfunction "1_1") (pintype "passive"))
      (node (ref "C4") (pin "1") (pinfunction "1_1") (pintype "passive"))
      (node (ref "C5") (pin "1") (pinfunction "1_1") (pintype "passive"))
      (node (ref "C6") (pin "2") (pinfunction "2_2") (pintype "passive"))
      (node (ref "C7") (pin "2") (pinfunction "2_2") (pintype "passive"))
      (node (ref "C8") (pin "2") (pinfunction "2_2") (pintype "passive"))
      (node (ref "C9") (pin "1") (pinfunction "1_1") (pintype "passive"))
      (node (ref "InLand_Header") (pin "14") (pinfunction "14_14") (pintype "passive"))
      (node (ref "InLand_Header") (pin "20") (pinfunction "20_20") (pintype "passive"))
      (node (ref "InLand_Header") (pin "25") (pinfunction "25_25") (pintype "passive"))
      (node (ref "InLand_Header") (pin "30") (pinfunction "30_30") (pintype "passive"))
      (node (ref "InLand_Header") (pin "34") (pinfunction "34_34") (pintype "passive"))
      (node (ref "InLand_Header") (pin "39") (pinfunction "39_39") (pintype "passive"))
      (node (ref "InLand_Header") (pin "6") (pinfunction "6_6") (pintype "passive"))
      (node (ref "InLand_Header") (pin "9") (pinfunction "9_9") (pintype "passive"))
      (node (ref "J1") (pin "2") (pinfunction "2_2") (pintype "passive"))
      (node (ref "L3") (pin "1") (pinfunction "1_1") (pintype "passive"))
      (node (ref "P1") (pin "1") (pinfunction "1_1") (pintype "passive"))
      (node (ref "R1") (pin "1") (pinfunction "1_1") (pintype "passive"))
      (node (ref "R10") (pin "1") (pinfunction "1_1") (pintype "passive"))
      (node (ref "R2") (pin "1") (pinfunction "1_1") (pintype "passive"))
      (node (ref "R22") (pin "1") (pinfunction "1_1") (pintype "passive"))
      (node (ref "S2") (pin "2") (pinfunction "2_2") (pintype "passive"))
      (node (ref "S2") (pin "3") (pinfunction "3_3") (pintype "passive"))
      (node (ref "Shoreline_Header") (pin "14") (pinfunction "14_14") (pintype "passive"))
      (node (ref "Shoreline_Header") (pin "20") (pinfunction "20_20") (pintype "passive"))
      (node (ref "Shoreline_Header") (pin "25") (pinfunction "25_25") (pintype "passive"))
      (node (ref "Shoreline_Header") (pin "30") (pinfunction "30_30") (pintype "passive"))
      (node (ref "Shoreline_Header") (pin "34") (pinfunction "34_34") (pintype "passive"))
      (node (ref "Shoreline_Header") (pin "39") (pinfunction "39_39") (pintype "passive"))
      (node (ref "Shoreline_Header") (pin "6") (pinfunction "6_6") (pintype "passive"))
      (node (ref "Shoreline_Header") (pin "9") (pinfunction "9_9") (pintype "passive"))
      (node (ref "U1") (pin "30") (pinfunction "XOSC_Q1_30") (pintype "input"))
      (node (ref "U1") (pin "33") (pinfunction "PAD_33") (pintype "passive"))
      (node (ref "U2") (pin "2") (pinfunction "NC_2") (pintype "passive"))
      (node (ref "U2") (pin "5") (pinfunction "GND_5") (pintype "passive"))
      (node (ref "U2") (pin "7") (pinfunction "PAD_7") (pintype "passive"))
      (node (ref "U3") (pin "1") (pinfunction "GND_1") (pintype "passive"))
      (node (ref "U3") (pin "11") (pinfunction "GND_11") (pintype "passive"))
      (node (ref "U3") (pin "12") (pinfunction "GND_12") (pintype "passive"))
      (node (ref "U3") (pin "15") (pinfunction "GND_15") (pintype "passive"))
      (node (ref "U3") (pin "19") (pinfunction "GND_19") (pintype "passive"))
      (node (ref "U3") (pin "21") (pinfunction "GND_21") (pintype "passive"))
      (node (ref "U3") (pin "22") (pinfunction "GND_22") (pintype "passive"))
      (node (ref "U3") (pin "27") (pinfunction "GND_27") (pintype "passive"))
      (node (ref "U3") (pin "28") (pinfunction "GND_28") (pintype "passive"))
      (node (ref "U3") (pin "29") (pinfunction "PAD_29") (pintype "passive"))
      (node (ref "U3") (pin "6") (pinfunction "GND_6") (pintype "passive"))
      (node (ref "U3") (pin "8") (pinfunction "GND_8") (pintype "passive"))
      (node (ref "U3") (pin "9") (pinfunction "GND_9") (pintype "passive"))
      (node (ref "U4") (pin "1") (pinfunction "G_1") (pintype "passive"))
      (node (ref "U4") (pin "3") (pinfunction "G_3") (pintype "passive"))
      (node (ref "U4") (pin "4") (pinfunction "G_4") (pintype "passive"))
      (node (ref "U4") (pin "6") (pinfunction "G_6") (pintype "passive"))
      (node (ref "U4") (pin "7") (pinfunction "G_7") (pintype "passive"))
      (node (ref "U4") (pin "8") (pinfunction "G_8") (pintype "passive"))
      (node (ref "U5") (pin "1") (pinfunction "GND_1") (pintype "passive"))
      (node (ref "U6") (pin "1") (pinfunction "GND_1") (pintype "passive"))
      (node (ref "U7") (pin "2") (pinfunction "GND_2") (pintype "passive"))
    )
    (net (code "36") (name "Net-(C21-Pad1)") (class "Default")
      (node (ref "C21") (pin "1") (pinfunction "1_1") (pintype "passive"))
      (node (ref "C25") (pin "2") (pinfunction "2_2") (pintype "passive"))
      (node (ref "L5") (pin "1") (pinfunction "1_1") (pintype "passive"))
      (node (ref "L6") (pin "2") (pinfunction "2_2") (pintype "passive"))
    )
    (net (code "37") (name "Net-(C22-Pad2)") (class "Default")
      (node (ref "C22") (pin "2") (pinfunction "2_2") (pintype "passive"))
      (node (ref "C24") (pin "1") (pinfunction "1_1") (pintype "passive"))
      (node (ref "L4") (pin "2") (pinfunction "2_2") (pintype "passive"))
    )
    (net (code "38") (name "Net-(C23-Pad1)") (class "Default")
      (node (ref "C23") (pin "1") (pinfunction "1_1") (pintype "passive"))
      (node (ref "C24") (pin "2") (pinfunction "2_2") (pintype "passive"))
      (node (ref "L4") (pin "1") (pinfunction "1_1") (pintype "passive"))
      (node (ref "L5") (pin "2") (pinfunction "2_2") (pintype "passive"))
    )
    (net (code "39") (name "Net-(C26-Pad2)") (class "Default")
      (node (ref "C26") (pin "2") (pinfunction "2_2") (pintype "passive"))
      (node (ref "L7") (pin "1") (pinfunction "1_1") (pintype "passive"))
      (node (ref "R9") (pin "2") (pinfunction "2_2") (pintype "passive"))
    )
    (net (code "40") (name "Net-(U1-DCPL)") (class "Default")
      (node (ref "C5") (pin "2") (pinfunction "2_2") (pintype "passive"))
      (node (ref "U1") (pin "6") (pinfunction "DCPL_6") (pintype "power_in"))
    )
    (net (code "41") (name "Net-(U1-DCPL_PFD_CHP)") (class "Default")
      (node (ref "C10") (pin "1") (pinfunction "1_1") (pintype "passive"))
      (node (ref "U1") (pin "26") (pinfunction "DCPL_PFD_CHP_26") (pintype "power_in"))
    )
    (net (code "42") (name "Net-(U1-DCPL_VCO)") (class "Default")
      (node (ref "C18") (pin "2") (pinfunction "2_2") (pintype "passive"))
      (node (ref "U1") (pin "21") (pinfunction "DCPL_VCO_21") (pintype "power_in"))
    )
    (net (code "43") (name "Net-(U1-DCPL_XOSC)") (class "Default")
      (node (ref "C13") (pin "1") (pinfunction "1_1") (pintype "passive"))
      (node (ref "U1") (pin "29") (pinfunction "DCPL_XOSC_29") (pintype "power_in"))
    )
    (net (code "44") (name "Net-(U1-EXT_XOSC)") (class "Default")
      (node (ref "C15") (pin "1") (pinfunction "1_1") (pintype "passive"))
      (node (ref "U1") (pin "32") (pinfunction "EXT_XOSC_32") (pintype "input"))
    )
    (net (code "45") (name "Net-(U1-LNA_N)") (class "Default")
      (node (ref "C19") (pin "1") (pinfunction "1_1") (pintype "passive"))
      (node (ref "L1") (pin "2") (pinfunction "2_2") (pintype "passive"))
      (node (ref "L2") (pin "2") (pinfunction "2_2") (pintype "passive"))
      (node (ref "U1") (pin "20") (pinfunction "LNA_N_20") (pintype "output"))
    )
    (net (code "46") (name "Net-(U1-LNA_P)") (class "Default")
      (node (ref "C20") (pin "1") (pinfunction "1_1") (pintype "passive"))
      (node (ref "L2") (pin "1") (pinfunction "1_1") (pintype "passive"))
      (node (ref "L3") (pin "2") (pinfunction "2_2") (pintype "passive"))
      (node (ref "U1") (pin "19") (pinfunction "LNA_P_19") (pintype "output"))
    )
    (net (code "47") (name "Net-(U1-LPF0)") (class "Default")
      (node (ref "C16") (pin "2") (pinfunction "2_2") (pintype "passive"))
      (node (ref "U1") (pin "23") (pinfunction "LPF0_23") (pintype "output"))
    )
    (net (code "48") (name "Net-(U1-LPF1)") (class "Default")
      (node (ref "C16") (pin "1") (pinfunction "1_1") (pintype "passive"))
      (node (ref "U1") (pin "24") (pinfunction "LPF1_24") (pintype "output"))
    )
    (net (code "49") (name "Net-(U1-PA)") (class "Default")
      (node (ref "C22") (pin "1") (pinfunction "1_1") (pintype "passive"))
      (node (ref "L7") (pin "2") (pinfunction "2_2") (pintype "passive"))
      (node (ref "U1") (pin "17") (pinfunction "PA_17") (pintype "output"))
    )
    (net (code "50") (name "Net-(U1-RBIAS)") (class "Default")
      (node (ref "R10") (pin "2") (pinfunction "2_2") (pintype "passive"))
      (node (ref "U1") (pin "14") (pinfunction "RBIAS_14") (pintype "output"))
    )
    (net (code "51") (name "Net-(U1-TRX_SW)") (class "Default")
      (node (ref "C23") (pin "2") (pinfunction "2_2") (pintype "passive"))
      (node (ref "U1") (pin "18") (pinfunction "TRX_SW_18") (pintype "output"))
    )
    (net (code "52") (name "Net-(U2-PG)") (class "Default")
      (node (ref "R15") (pin "1") (pinfunction "1_1") (pintype "passive"))
      (node (ref "U2") (pin "3") (pinfunction "PG_3") (pintype "passive"))
    )
    (net (code "53") (name "Net-(U3-ANT)") (class "Default")
      (node (ref "J1") (pin "1") (pinfunction "1_1") (pintype "passive"))
      (node (ref "U3") (pin "7") (pinfunction "ANT_7") (pintype "passive"))
    )
    (net (code "54") (name "Net-(U3-EN)") (class "Default")
      (node (ref "R20") (pin "2") (pinfunction "2_2") (pintype "passive"))
      (node (ref "U3") (pin "3") (pinfunction "EN_3") (pintype "passive"))
    )
    (net (code "55") (name "Net-(U3-RX)") (class "Default")
      (node (ref "C20") (pin "2") (pinfunction "2_2") (pintype "passive"))
      (node (ref "L1") (pin "1") (pinfunction "1_1") (pintype "passive"))
      (node (ref "U3") (pin "18") (pinfunction "RX_18") (pintype "passive"))
    )
    (net (code "56") (name "Net-(U3-SAW1)") (class "Default")
      (node (ref "L8") (pin "1") (pinfunction "1_1") (pintype "passive"))
      (node (ref "U3") (pin "10") (pinfunction "SAW1_10") (pintype "passive"))
    )
    (net (code "57") (name "Net-(U3-SAW2)") (class "Default")
      (node (ref "L9") (pin "2") (pinfunction "2_2") (pintype "passive"))
      (node (ref "U3") (pin "13") (pinfunction "SAW2_13") (pintype "passive"))
    )
    (net (code "58") (name "Net-(U3-TX)") (class "Default")
      (node (ref "C21") (pin "2") (pinfunction "2_2") (pintype "passive"))
      (node (ref "L6") (pin "1") (pinfunction "1_1") (pintype "passive"))
      (node (ref "U3") (pin "20") (pinfunction "TX_20") (pintype "passive"))
    )
    (net (code "59") (name "Net-(U4-INPUT)") (class "Default")
      (node (ref "L8") (pin "2") (pinfunction "2_2") (pintype "passive"))
      (node (ref "U4") (pin "2") (pinfunction "INPUT_2") (pintype "passive"))
    )
    (net (code "60") (name "Net-(U4-OUTPUT)") (class "Default")
      (node (ref "L9") (pin "1") (pinfunction "1_1") (pintype "passive"))
      (node (ref "U4") (pin "5") (pinfunction "OUTPUT_5") (pintype "passive"))
    )
    (net (code "61") (name "Net-(U7-OUT)") (class "Default")
      (node (ref "C15") (pin "2") (pinfunction "2_2") (pintype "passive"))
      (node (ref "U7") (pin "3") (pinfunction "OUT_3") (pintype "passive"))
    )
    (net (code "62") (name "VREG") (class "Default")
      (node (ref "C11") (pin "1") (pinfunction "1_1") (pintype "passive"))
      (node (ref "C12") (pin "2") (pinfunction "2_2") (pintype "passive"))
      (node (ref "C14") (pin "1") (pinfunction "1_1") (pintype "passive"))
      (node (ref "C17") (pin "2") (pinfunction "2_2") (pintype "passive"))
      (node (ref "C2") (pin "1") (pinfunction "1_1") (pintype "passive"))
      (node (ref "C26") (pin "1") (pinfunction "1_1") (pintype "passive"))
      (node (ref "C27") (pin "1") (pinfunction "1_1") (pintype "passive"))
      (node (ref "C28") (pin "2") (pinfunction "2_2") (pintype "passive"))
      (node (ref "C29") (pin "2") (pinfunction "2_2") (pintype "passive"))
      (node (ref "C3") (pin "2") (pinfunction "2_2") (pintype "passive"))
      (node (ref "C4") (pin "2") (pinfunction "2_2") (pintype "passive"))
      (node (ref "C6") (pin "1") (pinfunction "1_1") (pintype "passive"))
      (node (ref "C7") (pin "1") (pinfunction "1_1") (pintype "passive"))
      (node (ref "C8") (pin "1") (pinfunction "1_1") (pintype "passive"))
      (node (ref "C9") (pin "2") (pinfunction "2_2") (pintype "passive"))
      (node (ref "P1") (pin "2") (pinfunction "2_2") (pintype "passive"))
      (node (ref "R11") (pin "2") (pinfunction "2_2") (pintype "passive"))
      (node (ref "R15") (pin "2") (pinfunction "2_2") (pintype "passive"))
      (node (ref "R9") (pin "1") (pinfunction "1_1") (pintype "passive"))
      (node (ref "U1") (pin "1") (pinfunction "VDD_GUARD_1") (pintype "power_in"))
      (node (ref "U1") (pin "12") (pinfunction "DVDD_12") (pintype "power_in"))
      (node (ref "U1") (pin "13") (pinfunction "AVDD_IF_13") (pintype "power_in"))
      (node (ref "U1") (pin "15") (pinfunction "AVDD_RF_15") (pintype "power_in"))
      (node (ref "U1") (pin "22") (pinfunction "AVDD_SYNTH1_22") (pintype "power_in"))
      (node (ref "U1") (pin "25") (pinfunction "AVDD_PFD_CHP_25") (pintype "power_in"))
      (node (ref "U1") (pin "27") (pinfunction "AVDD_SYNTH2_27") (pintype "power_in"))
      (node (ref "U1") (pin "28") (pinfunction "AVDD_XOSC_28") (pintype "power_in"))
      (node (ref "U1") (pin "5") (pinfunction "DVDD_5") (pintype "power_in"))
      (node (ref "U2") (pin "1") (pinfunction "OUT_1") (pintype "passive"))
      (node (ref "U3") (pin "17") (pinfunction "VCC_RX_17") (pintype "passive"))
      (node (ref "U5") (pin "3") (pinfunction "VDD_3") (pintype "passive"))
      (node (ref "U7") (pin "4") (pinfunction "VCC_4") (pintype "passive"))
    )
    (net (code "63") (name "unconnected-(P1-Pad9)") (class "Default")
      (node (ref "P1") (pin "9") (pinfunction "9_9") (pintype "passive+no_connect"))
    )
    (net (code "64") (name "unconnected-(U1-N.C.-Pad16)") (class "Default")
      (node (ref "U1") (pin "16") (pinfunction "N.C._16") (pintype "passive+no_connect"))
    )
    (net (code "65") (name "unconnected-(U1-XOSC_Q2-Pad31)") (class "Default")
      (node (ref "U1") (pin "31") (pinfunction "XOSC_Q2_31") (pintype "input+no_connect"))
    )
    (net (code "66") (name "unconnected-(U3-NC-Pad14)") (class "Default")
      (node (ref "U3") (pin "14") (pinfunction "NC_14") (pintype "passive+no_connect"))
    )
    (net (code "67") (name "unconnected-(U3-NC-Pad16)") (class "Default")
      (node (ref "U3") (pin "16") (pinfunction "NC_16") (pintype "passive+no_connect"))
    )
    (net (code "68") (name "unconnected-(U3-NC-Pad25)") (class "Default")
      (node (ref "U3") (pin "25") (pinfunction "NC_25") (pintype "passive+no_connect"))
    )
    (net (code "69") (name "unconnected-(U7-NC-Pad1)") (class "Default")
      (node (ref "U7") (pin "1") (pinfunction "NC_1") (pintype "passive+no_connect"))
    )
  )
)
